# USB-ESP32.net
KiCad netlist of a schematic drawn in Altium Designer
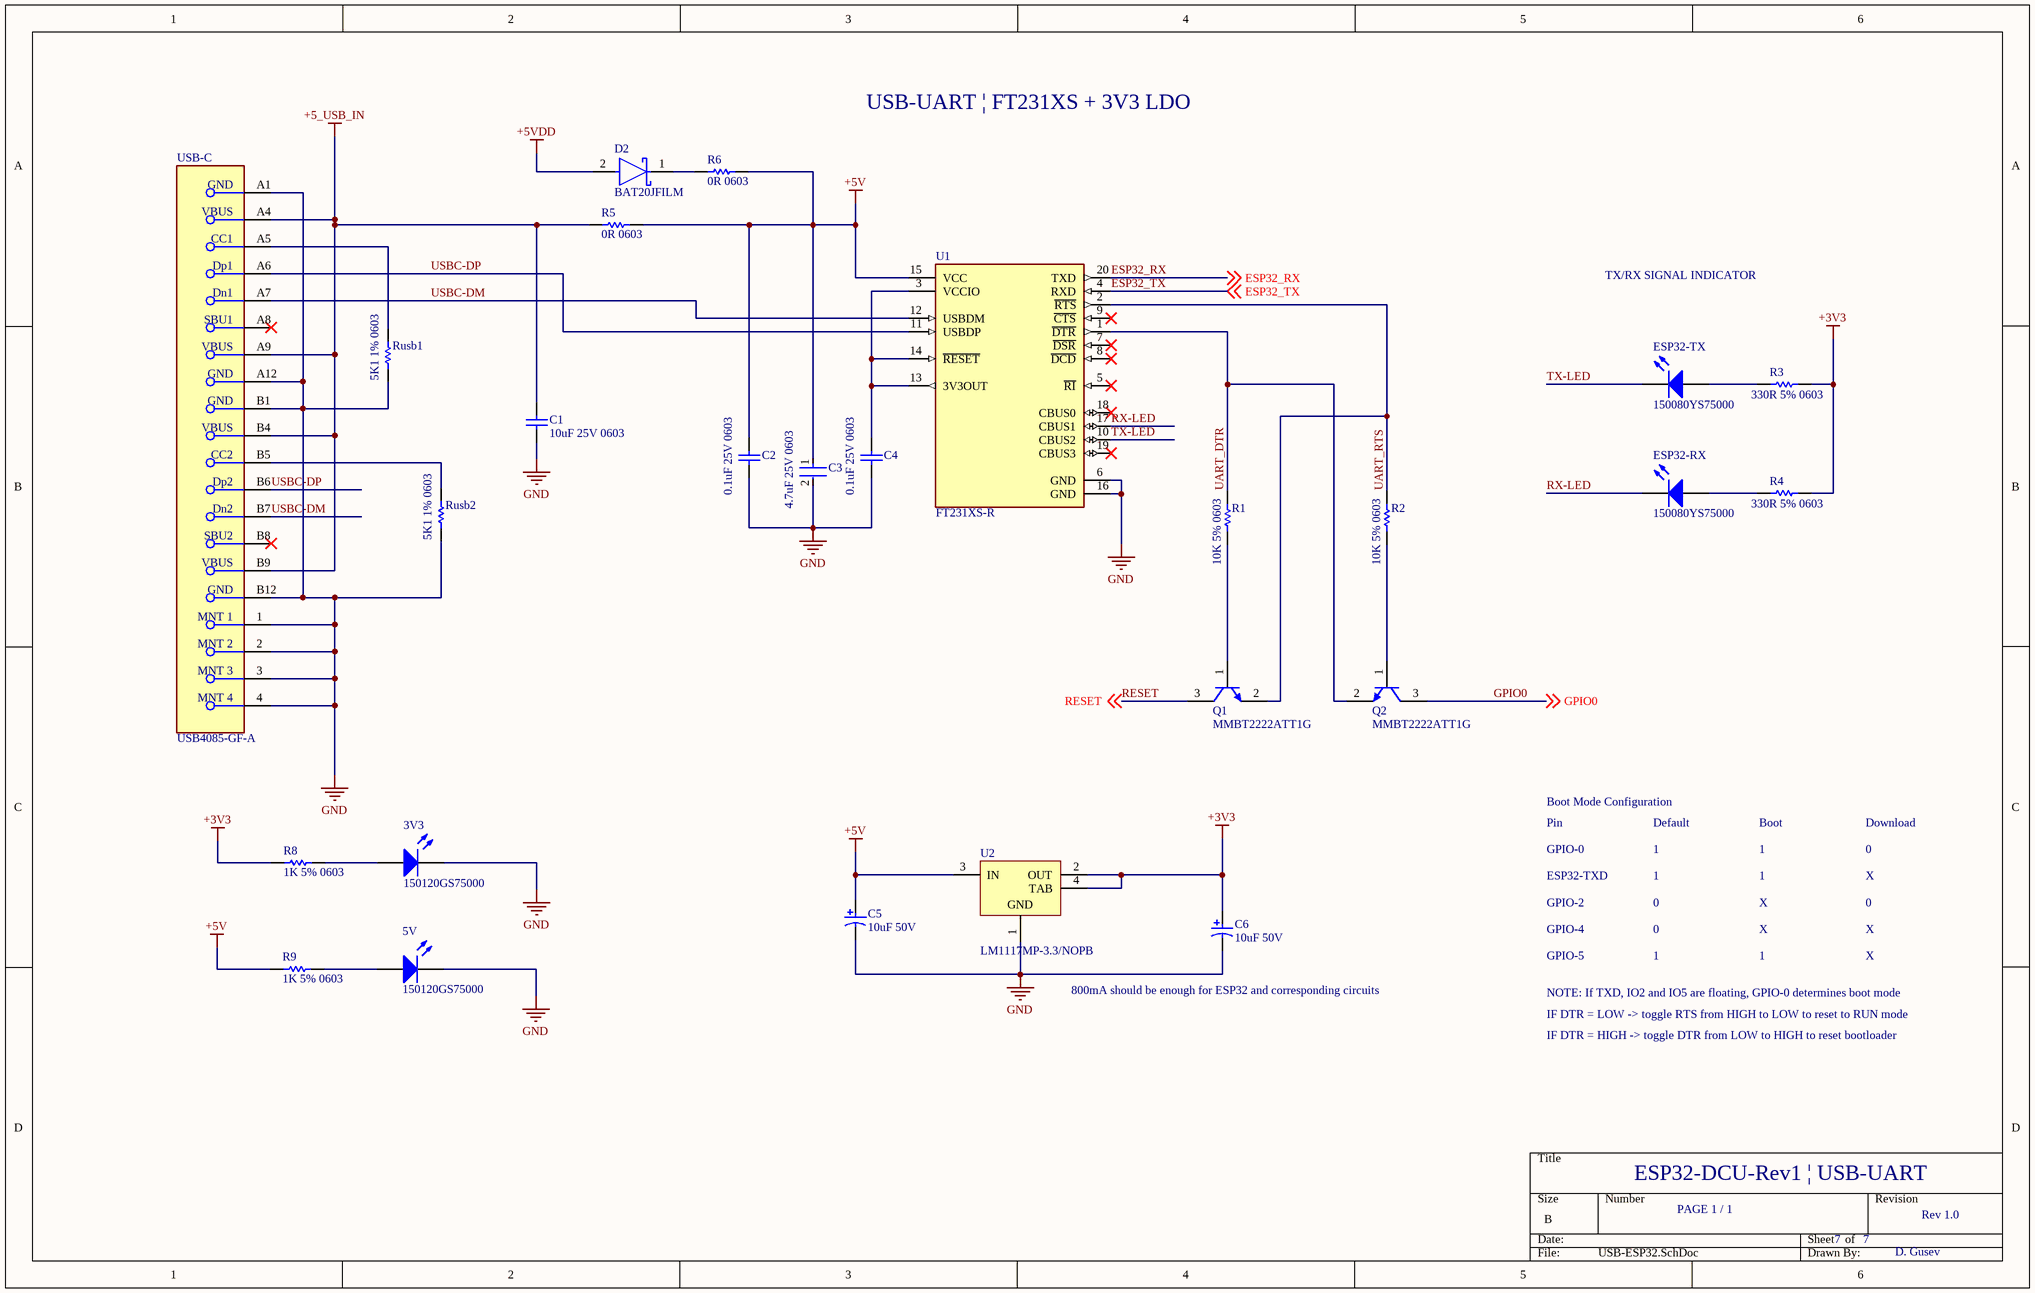
[diagram p0: USB-ESP32.SchDoc]

(export (version "E")
  (design (tool "Eeschema 10.0.6"))
  (components
    (comp (ref "3V3")
      (value "150120GS75000")
      (footprint "1206_A")
      (description "SMD mono-color Chip LED, WL-SMCW, Green")
      (fields (field (name "MANUFACTURER") "Wuerth Elektronik"))
      (libsource (lib "Altium Content Vault") (part "WE-LED_K1A2-2"))
    )
    (comp (ref "5V")
      (value "150120GS75000")
      (footprint "1206_A")
      (description "SMD mono-color Chip LED, WL-SMCW, Green")
      (fields (field (name "MANUFACTURER") "Wuerth Elektronik"))
      (libsource (lib "Altium Content Vault") (part "WE-LED_K1A2-2"))
    )
    (comp (ref "C1")
      (value "10uF 25V 0603")
      (footprint "CAPC1608X100X20VL10T10")
      (description "Chip Capacitor, 10 uF, +/- 20%, 25 V, -55 to 85 degC, 0603 (1608 Metric), RoHS, Tape and Reel")
      (fields (field (name "MANUFACTURER") "TDK") (field (name "TOLERANCE") "±20%"))
      (libsource (lib "Altium Content Vault") (part "CAP-NP-2"))
    )
    (comp (ref "C2")
      (value "0.1uF 25V 0603")
      (footprint "CAPC1608X90X35LL10T15")
      (fields (field (name "PART NUMBER") "GRM188R71E104KA01D") (field (name "MANUFACTURER") "Murata"))
      (libsource (lib "Altium Content Vault") (part "CAP"))
    )
    (comp (ref "C3")
      (value "4.7uF 25V 0603")
      (footprint "FP-GRM188-0_15-IPC_C")
      (description "Chip Multilayer Ceramic Capacitors for General Purpose, 0603, 4.7uF, X5R, 15%, 10%, 25V")
      (fields (field (name "VOLTAGE") "25V") (field (name "TOLERANCE") "10%"))
      (libsource (lib "Altium Content Vault") (part "02cd4be3c70576c341d710602a673aa"))
    )
    (comp (ref "C4")
      (value "0.1uF 25V 0603")
      (footprint "CAPC1608X90X35LL10T15")
      (fields (field (name "PART NUMBER") "GRM188R71E104KA01D") (field (name "MANUFACTURER") "Murata"))
      (libsource (lib "Altium Content Vault") (part "CAP"))
    )
    (comp (ref "C5")
      (value "10uF 50V")
      (footprint "PNSC-FK-V-D_V")
      (fields (field (name "MANUFACTURER") "Panasonic"))
      (libsource (lib "Altium Content Vault") (part "CAP-P-2"))
    )
    (comp (ref "C6")
      (value "10uF 50V")
      (footprint "PNSC-FK-V-D_V")
      (fields (field (name "MANUFACTURER") "Panasonic"))
      (libsource (lib "Altium Content Vault") (part "CAP-P-2"))
    )
    (comp (ref "D2")
      (value "BAT20JFILM")
      (footprint "FP-BAT20JFILM-MFG")
      (description "DIODE SCHOTTKY 23V 1A SOD323")
      (libsource (lib "Altium Content Vault") (part "fefb30dabb5d097ae2f038500735429"))
    )
    (comp (ref "ESP32-RX")
      (value "150080YS75000")
      (footprint "0805_A")
      (description "SMD mono-color Chip LED, WL-SMCW, Yellow")
      (fields (field (name "MANUFACTURER") "Wuerth Elektronik"))
      (libsource (lib "Altium Content Vault") (part "WE-LED_K1A2-2"))
    )
    (comp (ref "ESP32-TX")
      (value "150080YS75000")
      (footprint "0805_A")
      (description "SMD mono-color Chip LED, WL-SMCW, Yellow")
      (fields (field (name "MANUFACTURER") "Wuerth Elektronik"))
      (libsource (lib "Altium Content Vault") (part "WE-LED_K1A2-2"))
    )
    (comp (ref "Q1")
      (value "MMBT2222ATT1G")
      (footprint "ONSC-SC-75-3-463-01_V")
      (description "General Purpose Transistor, NPN Silicon, 3-Pin SC-75, Pb-Free, Tape and Reel")
      (fields (field (name "MANUFACTURER") "On Semiconductor"))
      (libsource (lib "Altium Content Vault") (part "ONSC-NPN-B1E2C3-3"))
    )
    (comp (ref "Q2")
      (value "MMBT2222ATT1G")
      (footprint "ONSC-SC-75-3-463-01_V")
      (description "General Purpose Transistor, NPN Silicon, 3-Pin SC-75, Pb-Free, Tape and Reel")
      (fields (field (name "MANUFACTURER") "On Semiconductor"))
      (libsource (lib "Altium Content Vault") (part "ONSC-NPN-B1E2C3-3"))
    )
    (comp (ref "R1")
      (value "10K 5% 0603")
      (footprint "RESC1608X55X25ML10T15")
      (description "Chip Resistor, 10 KOhm, +/- 1%, 01 W, -55 to 155 degC, 0603 (1608 Metric), RoHS, Tape and Reel")
      (fields (field (name "MANUFACTURER") "Yageo") (field (name "TOLERANCE") "1%"))
      (libsource (lib "Altium Content Vault") (part "RES-2"))
    )
    (comp (ref "R2")
      (value "10K 5% 0603")
      (footprint "RESC1608X55X25ML10T15")
      (description "Chip Resistor, 10 KOhm, +/- 1%, 01 W, -55 to 155 degC, 0603 (1608 Metric), RoHS, Tape and Reel")
      (fields (field (name "MANUFACTURER") "Yageo") (field (name "TOLERANCE") "1%"))
      (libsource (lib "Altium Content Vault") (part "RES-2"))
    )
    (comp (ref "R3")
      (value "330R 5% 0603")
      (footprint "RESC1608X55X25NL10T15")
      (description "Chip Resistor, 330 Ohm, +/- 1%, 0.1 W, -55 to 155 degC, 0603 (1608 Metric), RoHS, Tape and Reel")
      (fields (field (name "TOLERANCE") "10%"))
      (libsource (lib "Altium Content Vault") (part "RES-2"))
    )
    (comp (ref "R4")
      (value "330R 5% 0603")
      (footprint "RESC1608X55X25NL10T15")
      (description "Chip Resistor, 330 Ohm, +/- 1%, 0.1 W, -55 to 155 degC, 0603 (1608 Metric), RoHS, Tape and Reel")
      (fields (field (name "TOLERANCE") "10%"))
      (libsource (lib "Altium Content Vault") (part "RES-2"))
    )
    (comp (ref "R5")
      (value "0R 0603")
      (footprint "RESC1608X55X25ML10T15")
      (description "Chip Resistor, 0 Ohm, +/- 5%, 0.1 W, -55 to 155 degC, 0603 (1608 Metric), RoHS, Tape and Reel")
      (fields (field (name "TOLERANCE") "5%") (field (name "MANUFACTURER") "Yageo"))
      (libsource (lib "Altium Content Vault") (part "RES-2"))
    )
    (comp (ref "R6")
      (value "0R 0603")
      (footprint "RESC1608X55X25ML10T15")
      (description "Chip Resistor, 0 Ohm, +/- 5%, 0.1 W, -55 to 155 degC, 0603 (1608 Metric), RoHS, Tape and Reel")
      (fields (field (name "TOLERANCE") "5%") (field (name "MANUFACTURER") "Yageo"))
      (libsource (lib "Altium Content Vault") (part "RES-2"))
    )
    (comp (ref "R8")
      (value "1K 5% 0603")
      (footprint "RESC1608X55X25NL10T15")
      (description "Chip Resistor, 1 KOhm, +/-1%, 0.1 W, -55 to 155 degC, 0603 (1608 Metric), RoHS, Tape and Reel")
      (fields (field (name "MANUFACTURER") "Yageo"))
      (libsource (lib "Altium Content Vault") (part "RES-2"))
    )
    (comp (ref "R9")
      (value "1K 5% 0603")
      (footprint "RESC1608X55X25NL10T15")
      (description "Chip Resistor, 1 KOhm, +/-1%, 0.1 W, -55 to 155 degC, 0603 (1608 Metric), RoHS, Tape and Reel")
      (fields (field (name "MANUFACTURER") "Yageo"))
      (libsource (lib "Altium Content Vault") (part "RES-2"))
    )
    (comp (ref "Rusb1")
      (value "5K1 1% 0603")
      (footprint "RESC1608X55X25ML10T15")
      (fields (field (name "MANUFACTURER") "Yageo") (field (name "PART NUMBER") "RC0603FR-075K1L"))
      (libsource (lib "Altium Content Vault") (part "RES"))
    )
    (comp (ref "Rusb2")
      (value "5K1 1% 0603")
      (footprint "RESC1608X55X25ML10T15")
      (fields (field (name "MANUFACTURER") "Yageo") (field (name "PART NUMBER") "RC0603FR-075K1L"))
      (libsource (lib "Altium Content Vault") (part "RES"))
    )
    (comp (ref "U1")
      (value "FT231XS-R")
      (footprint "FP-SSOP-20-MFG")
      (description "IC USB SERIAL FULL UART 20SSOP")
      (libsource (lib "Altium Content Vault") (part "6ea930917329caabf1041b50a9b81b2"))
    )
    (comp (ref "U2")
      (value "LM1117MP-3.3/NOPB")
      (footprint "DCY0004A_L")
      (description "800mA Low-Dropout Linear Regulator, 4-pin SOT-223, Pb-Free")
      (fields (field (name "MANUFACTURER") "Texas Instruments"))
      (libsource (lib "Altium Content Vault") (part "PM-REG-LM1086-SOT4"))
    )
    (comp (ref "USB-C")
      (value "USB4085-GF-A")
      (footprint "FP-USB4085-GF-A-MFG")
      (description "CONN RCPT USB2.0 TYPEC 16POS")
      (fields
        (field (name "MANUFACTURER") "Global Connector Technology")
        (field (name "OCTOPART") "https://octopart.com/usb4085-gf-a-global+connector+technology-94773699")
      )
      (libsource (lib "Altium Content Vault") (part "f6997dba88850a18107ac0013977506"))
    )
  )
  (nets
    (net (code "1") (name "+3V3") (class "Default")
      (node (ref "C6") (pin "1") (pinfunction "1_1") (pintype "passive"))
      (node (ref "R3") (pin "2") (pinfunction "2_2") (pintype "passive"))
      (node (ref "R4") (pin "2") (pinfunction "2_2") (pintype "passive"))
      (node (ref "R8") (pin "1") (pinfunction "1_1") (pintype "passive"))
      (node (ref "U2") (pin "2") (pinfunction "OUT_2") (pintype "power_in"))
      (node (ref "U2") (pin "4") (pinfunction "TAB_4") (pintype "power_in"))
    )
    (net (code "2") (name "+5V") (class "Default")
      (node (ref "C2") (pin "2") (pinfunction "2_2") (pintype "passive"))
      (node (ref "C3") (pin "1") (pinfunction "1_1") (pintype "passive"))
      (node (ref "C5") (pin "1") (pinfunction "1_1") (pintype "passive"))
      (node (ref "R5") (pin "2") (pinfunction "2_2") (pintype "passive"))
      (node (ref "R6") (pin "2") (pinfunction "2_2") (pintype "passive"))
      (node (ref "R9") (pin "1") (pinfunction "1_1") (pintype "passive"))
      (node (ref "U1") (pin "15") (pinfunction "VCC_15") (pintype "power_in"))
      (node (ref "U2") (pin "3") (pinfunction "IN_3") (pintype "power_in"))
    )
    (net (code "3") (name "+5VDD") (class "Default")
      (node (ref "D2") (pin "2") (pinfunction "A_2") (pintype "passive"))
    )
    (net (code "4") (name "+5_USB_IN") (class "Default")
      (node (ref "C1") (pin "2") (pinfunction "2_2") (pintype "passive"))
      (node (ref "R5") (pin "1") (pinfunction "1_1") (pintype "passive"))
      (node (ref "USB-C") (pin "A4") (pinfunction "VBUS_A4") (pintype "power_in"))
      (node (ref "USB-C") (pin "A9") (pinfunction "VBUS_A9") (pintype "power_in"))
      (node (ref "USB-C") (pin "B4") (pinfunction "VBUS_B4") (pintype "power_in"))
      (node (ref "USB-C") (pin "B9") (pinfunction "VBUS_B9") (pintype "power_in"))
    )
    (net (code "5") (name "/RX-LED") (class "Default")
      (node (ref "ESP32-RX") (pin "1") (pinfunction "K_1") (pintype "passive"))
      (node (ref "U1") (pin "17") (pinfunction "CBUS1_17") (pintype "bidirectional"))
    )
    (net (code "6") (name "/TX-LED") (class "Default")
      (node (ref "ESP32-TX") (pin "1") (pinfunction "K_1") (pintype "passive"))
      (node (ref "U1") (pin "10") (pinfunction "CBUS2_10") (pintype "bidirectional"))
    )
    (net (code "7") (name "/UART_DTR") (class "Default")
      (node (ref "Q2") (pin "2") (pinfunction "E_2") (pintype "passive"))
      (node (ref "R1") (pin "2") (pinfunction "2_2") (pintype "passive"))
      (node (ref "U1") (pin "1") (pinfunction "~{DTR}_1") (pintype "output"))
    )
    (net (code "8") (name "/UART_RTS") (class "Default")
      (node (ref "Q1") (pin "2") (pinfunction "E_2") (pintype "passive"))
      (node (ref "R2") (pin "2") (pinfunction "2_2") (pintype "passive"))
      (node (ref "U1") (pin "2") (pinfunction "~{RTS}_2") (pintype "output"))
    )
    (net (code "9") (name "/USBC-DM") (class "Default")
      (node (ref "U1") (pin "12") (pinfunction "USBDM_12") (pintype "input"))
      (node (ref "USB-C") (pin "A7") (pinfunction "Dn1_A7") (pintype "passive"))
      (node (ref "USB-C") (pin "B7") (pinfunction "Dn2_B7") (pintype "passive"))
    )
    (net (code "10") (name "/USBC-DP") (class "Default")
      (node (ref "U1") (pin "11") (pinfunction "USBDP_11") (pintype "input"))
      (node (ref "USB-C") (pin "A6") (pinfunction "Dp1_A6") (pintype "passive"))
      (node (ref "USB-C") (pin "B6") (pinfunction "Dp2_B6") (pintype "passive"))
    )
    (net (code "11") (name "ESP32_RX") (class "Default")
      (node (ref "U1") (pin "20") (pinfunction "TXD_20") (pintype "output"))
    )
    (net (code "12") (name "ESP32_TX") (class "Default")
      (node (ref "U1") (pin "4") (pinfunction "RXD_4") (pintype "input"))
    )
    (net (code "13") (name "GND") (class "Default")
      (node (ref "3V3") (pin "1") (pinfunction "K_1") (pintype "passive"))
      (node (ref "5V") (pin "1") (pinfunction "K_1") (pintype "passive"))
      (node (ref "C1") (pin "1") (pinfunction "1_1") (pintype "passive"))
      (node (ref "C2") (pin "1") (pinfunction "1_1") (pintype "passive"))
      (node (ref "C3") (pin "2") (pinfunction "2_2") (pintype "passive"))
      (node (ref "C4") (pin "1") (pinfunction "1_1") (pintype "passive"))
      (node (ref "C5") (pin "2") (pinfunction "2_2") (pintype "passive"))
      (node (ref "C6") (pin "2") (pinfunction "2_2") (pintype "passive"))
      (node (ref "Rusb1") (pin "1") (pinfunction "1_1") (pintype "passive"))
      (node (ref "Rusb2") (pin "1") (pinfunction "1_1") (pintype "passive"))
      (node (ref "U1") (pin "16") (pinfunction "GND_16") (pintype "power_in"))
      (node (ref "U1") (pin "6") (pinfunction "GND_6") (pintype "power_in"))
      (node (ref "U2") (pin "1") (pinfunction "GND_1") (pintype "power_in"))
      (node (ref "USB-C") (pin "1") (pinfunction "MNT_1_1") (pintype "passive"))
      (node (ref "USB-C") (pin "2") (pinfunction "MNT_2_2") (pintype "passive"))
      (node (ref "USB-C") (pin "3") (pinfunction "MNT_3_3") (pintype "passive"))
      (node (ref "USB-C") (pin "4") (pinfunction "MNT_4_4") (pintype "passive"))
      (node (ref "USB-C") (pin "A1") (pinfunction "GND_A1") (pintype "power_in"))
      (node (ref "USB-C") (pin "A12") (pinfunction "GND_A12") (pintype "power_in"))
      (node (ref "USB-C") (pin "B1") (pinfunction "GND_B1") (pintype "power_in"))
      (node (ref "USB-C") (pin "B12") (pinfunction "GND_B12") (pintype "power_in"))
    )
    (net (code "14") (name "GPIO0") (class "Default")
      (node (ref "Q2") (pin "3") (pinfunction "C_3") (pintype "passive"))
    )
    (net (code "15") (name "Net-(3V3-A)") (class "Default")
      (node (ref "3V3") (pin "2") (pinfunction "A_2") (pintype "passive"))
      (node (ref "R8") (pin "2") (pinfunction "2_2") (pintype "passive"))
    )
    (net (code "16") (name "Net-(5V-A)") (class "Default")
      (node (ref "5V") (pin "2") (pinfunction "A_2") (pintype "passive"))
      (node (ref "R9") (pin "2") (pinfunction "2_2") (pintype "passive"))
    )
    (net (code "17") (name "Net-(D2-K)") (class "Default")
      (node (ref "D2") (pin "1") (pinfunction "K_1") (pintype "passive"))
      (node (ref "R6") (pin "1") (pinfunction "1_1") (pintype "passive"))
    )
    (net (code "18") (name "Net-(ESP32-RX-A)") (class "Default")
      (node (ref "ESP32-RX") (pin "2") (pinfunction "A_2") (pintype "passive"))
      (node (ref "R4") (pin "1") (pinfunction "1_1") (pintype "passive"))
    )
    (net (code "19") (name "Net-(ESP32-TX-A)") (class "Default")
      (node (ref "ESP32-TX") (pin "2") (pinfunction "A_2") (pintype "passive"))
      (node (ref "R3") (pin "1") (pinfunction "1_1") (pintype "passive"))
    )
    (net (code "20") (name "Net-(Q1-B)") (class "Default")
      (node (ref "Q1") (pin "1") (pinfunction "B_1") (pintype "passive"))
      (node (ref "R1") (pin "1") (pinfunction "1_1") (pintype "passive"))
    )
    (net (code "21") (name "Net-(Q2-B)") (class "Default")
      (node (ref "Q2") (pin "1") (pinfunction "B_1") (pintype "passive"))
      (node (ref "R2") (pin "1") (pinfunction "1_1") (pintype "passive"))
    )
    (net (code "22") (name "Net-(U1-3V3OUT)") (class "Default")
      (node (ref "C4") (pin "2") (pinfunction "2_2") (pintype "passive"))
      (node (ref "U1") (pin "13") (pinfunction "3V3OUT_13") (pintype "output"))
      (node (ref "U1") (pin "14") (pinfunction "~{RESET}_14") (pintype "input"))
      (node (ref "U1") (pin "3") (pinfunction "VCCIO_3") (pintype "power_in"))
    )
    (net (code "23") (name "Net-(USB-C-CC1)") (class "Default")
      (node (ref "Rusb1") (pin "2") (pinfunction "2_2") (pintype "passive"))
      (node (ref "USB-C") (pin "A5") (pinfunction "CC1_A5") (pintype "passive"))
    )
    (net (code "24") (name "Net-(USB-C-CC2)") (class "Default")
      (node (ref "Rusb2") (pin "2") (pinfunction "2_2") (pintype "passive"))
      (node (ref "USB-C") (pin "B5") (pinfunction "CC2_B5") (pintype "passive"))
    )
    (net (code "25") (name "RESET") (class "Default")
      (node (ref "Q1") (pin "3") (pinfunction "C_3") (pintype "passive"))
    )
    (net (code "26") (name "unconnected-(U1-CBUS0-Pad18)") (class "Default")
      (node (ref "U1") (pin "18") (pinfunction "CBUS0_18") (pintype "bidirectional+no_connect"))
    )
    (net (code "27") (name "unconnected-(U1-CBUS3-Pad19)") (class "Default")
      (node (ref "U1") (pin "19") (pinfunction "CBUS3_19") (pintype "bidirectional+no_connect"))
    )
    (net (code "28") (name "unconnected-(U1-~{CTS}-Pad9)") (class "Default")
      (node (ref "U1") (pin "9") (pinfunction "~{CTS}_9") (pintype "input+no_connect"))
    )
    (net (code "29") (name "unconnected-(U1-~{DCD}-Pad8)") (class "Default")
      (node (ref "U1") (pin "8") (pinfunction "~{DCD}_8") (pintype "input+no_connect"))
    )
    (net (code "30") (name "unconnected-(U1-~{DSR}-Pad7)") (class "Default")
      (node (ref "U1") (pin "7") (pinfunction "~{DSR}_7") (pintype "input+no_connect"))
    )
    (net (code "31") (name "unconnected-(U1-~{RI}-Pad5)") (class "Default")
      (node (ref "U1") (pin "5") (pinfunction "~{RI}_5") (pintype "input+no_connect"))
    )
    (net (code "32") (name "unconnected-(USB-C-SBU1-PadA8)") (class "Default")
      (node (ref "USB-C") (pin "A8") (pinfunction "SBU1_A8") (pintype "passive+no_connect"))
    )
    (net (code "33") (name "unconnected-(USB-C-SBU2-PadB8)") (class "Default")
      (node (ref "USB-C") (pin "B8") (pinfunction "SBU2_B8") (pintype "passive+no_connect"))
    )
  )
)
